# USB_Isolator_v1p00.net
KiCad netlist of a schematic drawn in EAGLE
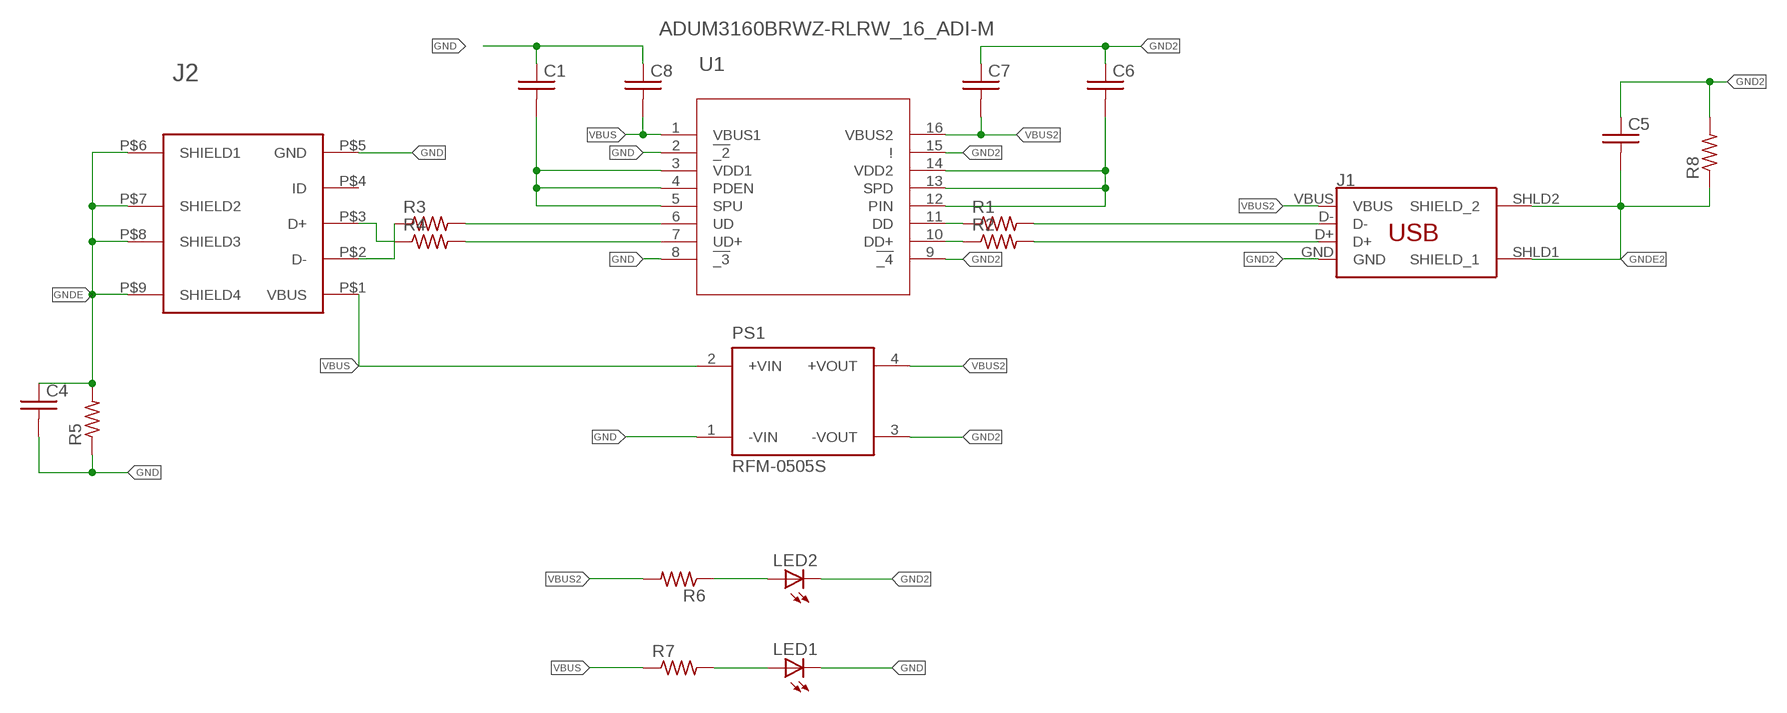
[diagram p0: schematic, sheet 1]

(export (version "E")
  (design (tool "Eeschema 10.0.6"))
  (components
    (comp (ref "C1")
      (value "C_0402")
      (footprint "eagle-import:0402")
      (libsource (lib "eagle-import") (part "C_0402"))
    )
    (comp (ref "C4")
      (value "C_0402")
      (footprint "eagle-import:0402")
      (libsource (lib "eagle-import") (part "C_0402"))
    )
    (comp (ref "C5")
      (value "C_0402")
      (footprint "eagle-import:0402")
      (libsource (lib "eagle-import") (part "C_0402"))
    )
    (comp (ref "C6")
      (value "C_0402")
      (footprint "eagle-import:0402")
      (libsource (lib "eagle-import") (part "C_0402"))
    )
    (comp (ref "C7")
      (value "C_0402")
      (footprint "eagle-import:0402")
      (libsource (lib "eagle-import") (part "C_0402"))
    )
    (comp (ref "C8")
      (value "C_0402")
      (footprint "eagle-import:0402")
      (libsource (lib "eagle-import") (part "C_0402"))
    )
    (comp (ref "J1")
      (value "USB_A")
      (footprint "eagle-import:USB_A_SMT")
      (libsource (lib "eagle-import") (part "USB_A"))
    )
    (comp (ref "J2")
      (value "USB_MICRO-B")
      (footprint "eagle-import:USB_MICRO-B")
      (libsource (lib "eagle-import") (part "USB_MICRO-B"))
    )
    (comp (ref "LED1")
      (value "LED_0805_GREEN")
      (footprint "eagle-import:LED_0805_GREEN")
      (libsource (lib "eagle-import") (part "LED_0805_GREEN"))
    )
    (comp (ref "LED2")
      (value "LED_0805_GREEN")
      (footprint "eagle-import:LED_0805_GREEN")
      (libsource (lib "eagle-import") (part "LED_0805_GREEN"))
    )
    (comp (ref "PS1")
      (value "RFM-0505S")
      (footprint "eagle-import:CONV_RFM-0505S")
      (fields (field (name "DIGI-KEY_PART_NUMBER") "945-3159-ND") (field (name "MF") "Recom Power"))
      (libsource (lib "eagle-import") (part "RFM-0505S"))
    )
    (comp (ref "R1")
      (value "R_0402")
      (footprint "eagle-import:0402")
      (libsource (lib "eagle-import") (part "R_0402"))
    )
    (comp (ref "R2")
      (value "R_0402")
      (footprint "eagle-import:0402")
      (libsource (lib "eagle-import") (part "R_0402"))
    )
    (comp (ref "R3")
      (value "R_0402")
      (footprint "eagle-import:0402")
      (libsource (lib "eagle-import") (part "R_0402"))
    )
    (comp (ref "R4")
      (value "R_0402")
      (footprint "eagle-import:0402")
      (libsource (lib "eagle-import") (part "R_0402"))
    )
    (comp (ref "R5")
      (value "R_0402")
      (footprint "eagle-import:0402")
      (libsource (lib "eagle-import") (part "R_0402"))
    )
    (comp (ref "R6")
      (value "R_0402")
      (footprint "eagle-import:0402")
      (libsource (lib "eagle-import") (part "R_0402"))
    )
    (comp (ref "R7")
      (value "R_0402")
      (footprint "eagle-import:0402")
      (libsource (lib "eagle-import") (part "R_0402"))
    )
    (comp (ref "R8")
      (value "R_0402")
      (footprint "eagle-import:0402")
      (libsource (lib "eagle-import") (part "R_0402"))
    )
    (comp (ref "U1")
      (value "ADUM3160BRWZ-RLRW_16_ADI-M")
      (footprint "eagle-import:RW_16_ADI-M")
      (fields
        (field (name "MANUFACTURER_PART_NUMBER") "ADUM3160BRWZ-RL")
        (field (name "COPYRIGHT") "Copyright (C) 2018 Accelerated Designs. All rights reserved")
      )
      (libsource (lib "eagle-import") (part "ADUM3160BRWZ-RLRW_16_ADI-M"))
    )
  )
  (nets
    (net (code "1") (name "GND") (class "Default")
      (node (ref "C1") (pin "P$1") (pinfunction "1_P$1") (pintype "passive"))
      (node (ref "C4") (pin "P$2") (pinfunction "2_P$2") (pintype "passive"))
      (node (ref "C8") (pin "P$1") (pinfunction "1_P$1") (pintype "passive"))
      (node (ref "J2") (pin "P$5") (pinfunction "GND_P$5") (pintype "bidirectional"))
      (node (ref "LED1") (pin "C") (pinfunction "C_C") (pintype "passive"))
      (node (ref "PS1") (pin "1") (pinfunction "-VIN_1") (pintype "input"))
      (node (ref "R5") (pin "P$1") (pinfunction "1_P$1") (pintype "passive"))
      (node (ref "U1") (pin "2") (pinfunction "~{_2}_2") (pintype "passive"))
      (node (ref "U1") (pin "8") (pinfunction "~{_3}_8") (pintype "passive"))
    )
    (net (code "2") (name "GND2") (class "Default")
      (node (ref "C5") (pin "P$1") (pinfunction "1_P$1") (pintype "passive"))
      (node (ref "C6") (pin "P$1") (pinfunction "1_P$1") (pintype "passive"))
      (node (ref "C7") (pin "P$1") (pinfunction "1_P$1") (pintype "passive"))
      (node (ref "J1") (pin "GND") (pinfunction "GND_GND") (pintype "power_in"))
      (node (ref "LED2") (pin "C") (pinfunction "C_C") (pintype "passive"))
      (node (ref "PS1") (pin "3") (pinfunction "-VOUT_3") (pintype "output"))
      (node (ref "R8") (pin "P$2") (pinfunction "2_P$2") (pintype "passive"))
      (node (ref "U1") (pin "15") (pinfunction "~_15") (pintype "passive"))
      (node (ref "U1") (pin "9") (pinfunction "~{_4}_9") (pintype "passive"))
    )
    (net (code "3") (name "GNDE") (class "Default")
      (node (ref "C4") (pin "P$1") (pinfunction "1_P$1") (pintype "passive"))
      (node (ref "J2") (pin "P$6") (pinfunction "SHIELD1_P$6") (pintype "bidirectional"))
      (node (ref "J2") (pin "P$7") (pinfunction "SHIELD2_P$7") (pintype "bidirectional"))
      (node (ref "J2") (pin "P$8") (pinfunction "SHIELD3_P$8") (pintype "bidirectional"))
      (node (ref "J2") (pin "P$9") (pinfunction "SHIELD4_P$9") (pintype "bidirectional"))
      (node (ref "R5") (pin "P$2") (pinfunction "2_P$2") (pintype "passive"))
    )
    (net (code "4") (name "GNDE2") (class "Default")
      (node (ref "C5") (pin "P$2") (pinfunction "2_P$2") (pintype "passive"))
      (node (ref "J1") (pin "SHLD1") (pinfunction "SHIELD_1_SHLD1") (pintype "bidirectional"))
      (node (ref "J1") (pin "SHLD2") (pinfunction "SHIELD_2_SHLD2") (pintype "bidirectional"))
      (node (ref "R8") (pin "P$1") (pinfunction "1_P$1") (pintype "passive"))
    )
    (net (code "5") (name "Net-(C1-2)") (class "Default")
      (node (ref "C1") (pin "P$2") (pinfunction "2_P$2") (pintype "passive"))
      (node (ref "U1") (pin "3") (pinfunction "VDD1_3") (pintype "power_in"))
      (node (ref "U1") (pin "4") (pinfunction "PDEN_4") (pintype "passive"))
      (node (ref "U1") (pin "5") (pinfunction "SPU_5") (pintype "passive"))
    )
    (net (code "6") (name "Net-(C6-2)") (class "Default")
      (node (ref "C6") (pin "P$2") (pinfunction "2_P$2") (pintype "passive"))
      (node (ref "U1") (pin "12") (pinfunction "PIN_12") (pintype "passive"))
      (node (ref "U1") (pin "13") (pinfunction "SPD_13") (pintype "passive"))
      (node (ref "U1") (pin "14") (pinfunction "VDD2_14") (pintype "power_in"))
    )
    (net (code "7") (name "Net-(J2-D+)") (class "Default")
      (node (ref "J2") (pin "P$3") (pinfunction "D+_P$3") (pintype "bidirectional"))
      (node (ref "R4") (pin "P$1") (pinfunction "1_P$1") (pintype "passive"))
    )
    (net (code "8") (name "Net-(J2-D-)") (class "Default")
      (node (ref "J2") (pin "P$2") (pinfunction "D-_P$2") (pintype "bidirectional"))
      (node (ref "R3") (pin "P$1") (pinfunction "1_P$1") (pintype "passive"))
    )
    (net (code "9") (name "Net-(R1-1)") (class "Default")
      (node (ref "R1") (pin "P$1") (pinfunction "1_P$1") (pintype "passive"))
      (node (ref "U1") (pin "11") (pinfunction "DD_11") (pintype "passive"))
    )
    (net (code "10") (name "Net-(R1-2)") (class "Default")
      (node (ref "J1") (pin "D-") (pinfunction "D-_D-") (pintype "bidirectional"))
      (node (ref "R1") (pin "P$2") (pinfunction "2_P$2") (pintype "passive"))
    )
    (net (code "11") (name "Net-(R2-1)") (class "Default")
      (node (ref "R2") (pin "P$1") (pinfunction "1_P$1") (pintype "passive"))
      (node (ref "U1") (pin "10") (pinfunction "DD+_10") (pintype "passive"))
    )
    (net (code "12") (name "Net-(R2-2)") (class "Default")
      (node (ref "J1") (pin "D+") (pinfunction "D+_D+") (pintype "bidirectional"))
      (node (ref "R2") (pin "P$2") (pinfunction "2_P$2") (pintype "passive"))
    )
    (net (code "13") (name "Net-(R3-2)") (class "Default")
      (node (ref "R3") (pin "P$2") (pinfunction "2_P$2") (pintype "passive"))
      (node (ref "U1") (pin "6") (pinfunction "UD_6") (pintype "passive"))
    )
    (net (code "14") (name "Net-(R4-2)") (class "Default")
      (node (ref "R4") (pin "P$2") (pinfunction "2_P$2") (pintype "passive"))
      (node (ref "U1") (pin "7") (pinfunction "UD+_7") (pintype "passive"))
    )
    (net (code "15") (name "Net-(R6-1)") (class "Default")
      (node (ref "LED2") (pin "A") (pinfunction "A_A") (pintype "passive"))
      (node (ref "R6") (pin "P$1") (pinfunction "1_P$1") (pintype "passive"))
    )
    (net (code "16") (name "Net-(R7-2)") (class "Default")
      (node (ref "LED1") (pin "A") (pinfunction "A_A") (pintype "passive"))
      (node (ref "R7") (pin "P$2") (pinfunction "2_P$2") (pintype "passive"))
    )
    (net (code "17") (name "VBUS") (class "Default")
      (node (ref "C8") (pin "P$2") (pinfunction "2_P$2") (pintype "passive"))
      (node (ref "J2") (pin "P$1") (pinfunction "VBUS_P$1") (pintype "bidirectional"))
      (node (ref "PS1") (pin "2") (pinfunction "+VIN_2") (pintype "input"))
      (node (ref "R7") (pin "P$1") (pinfunction "1_P$1") (pintype "passive"))
      (node (ref "U1") (pin "1") (pinfunction "VBUS1_1") (pintype "bidirectional"))
    )
    (net (code "18") (name "VBUS2") (class "Default")
      (node (ref "C7") (pin "P$2") (pinfunction "2_P$2") (pintype "passive"))
      (node (ref "J1") (pin "VBUS") (pinfunction "VBUS_VBUS") (pintype "power_in"))
      (node (ref "PS1") (pin "4") (pinfunction "+VOUT_4") (pintype "output"))
      (node (ref "R6") (pin "P$2") (pinfunction "2_P$2") (pintype "passive"))
      (node (ref "U1") (pin "16") (pinfunction "VBUS2_16") (pintype "bidirectional"))
    )
    (net (code "19") (name "unconnected-(J2-ID-PadP$4)") (class "Default")
      (node (ref "J2") (pin "P$4") (pinfunction "ID_P$4") (pintype "bidirectional"))
    )
  )
)
